# HypnosV3_4.net
KiCad netlist of a schematic drawn in EAGLE
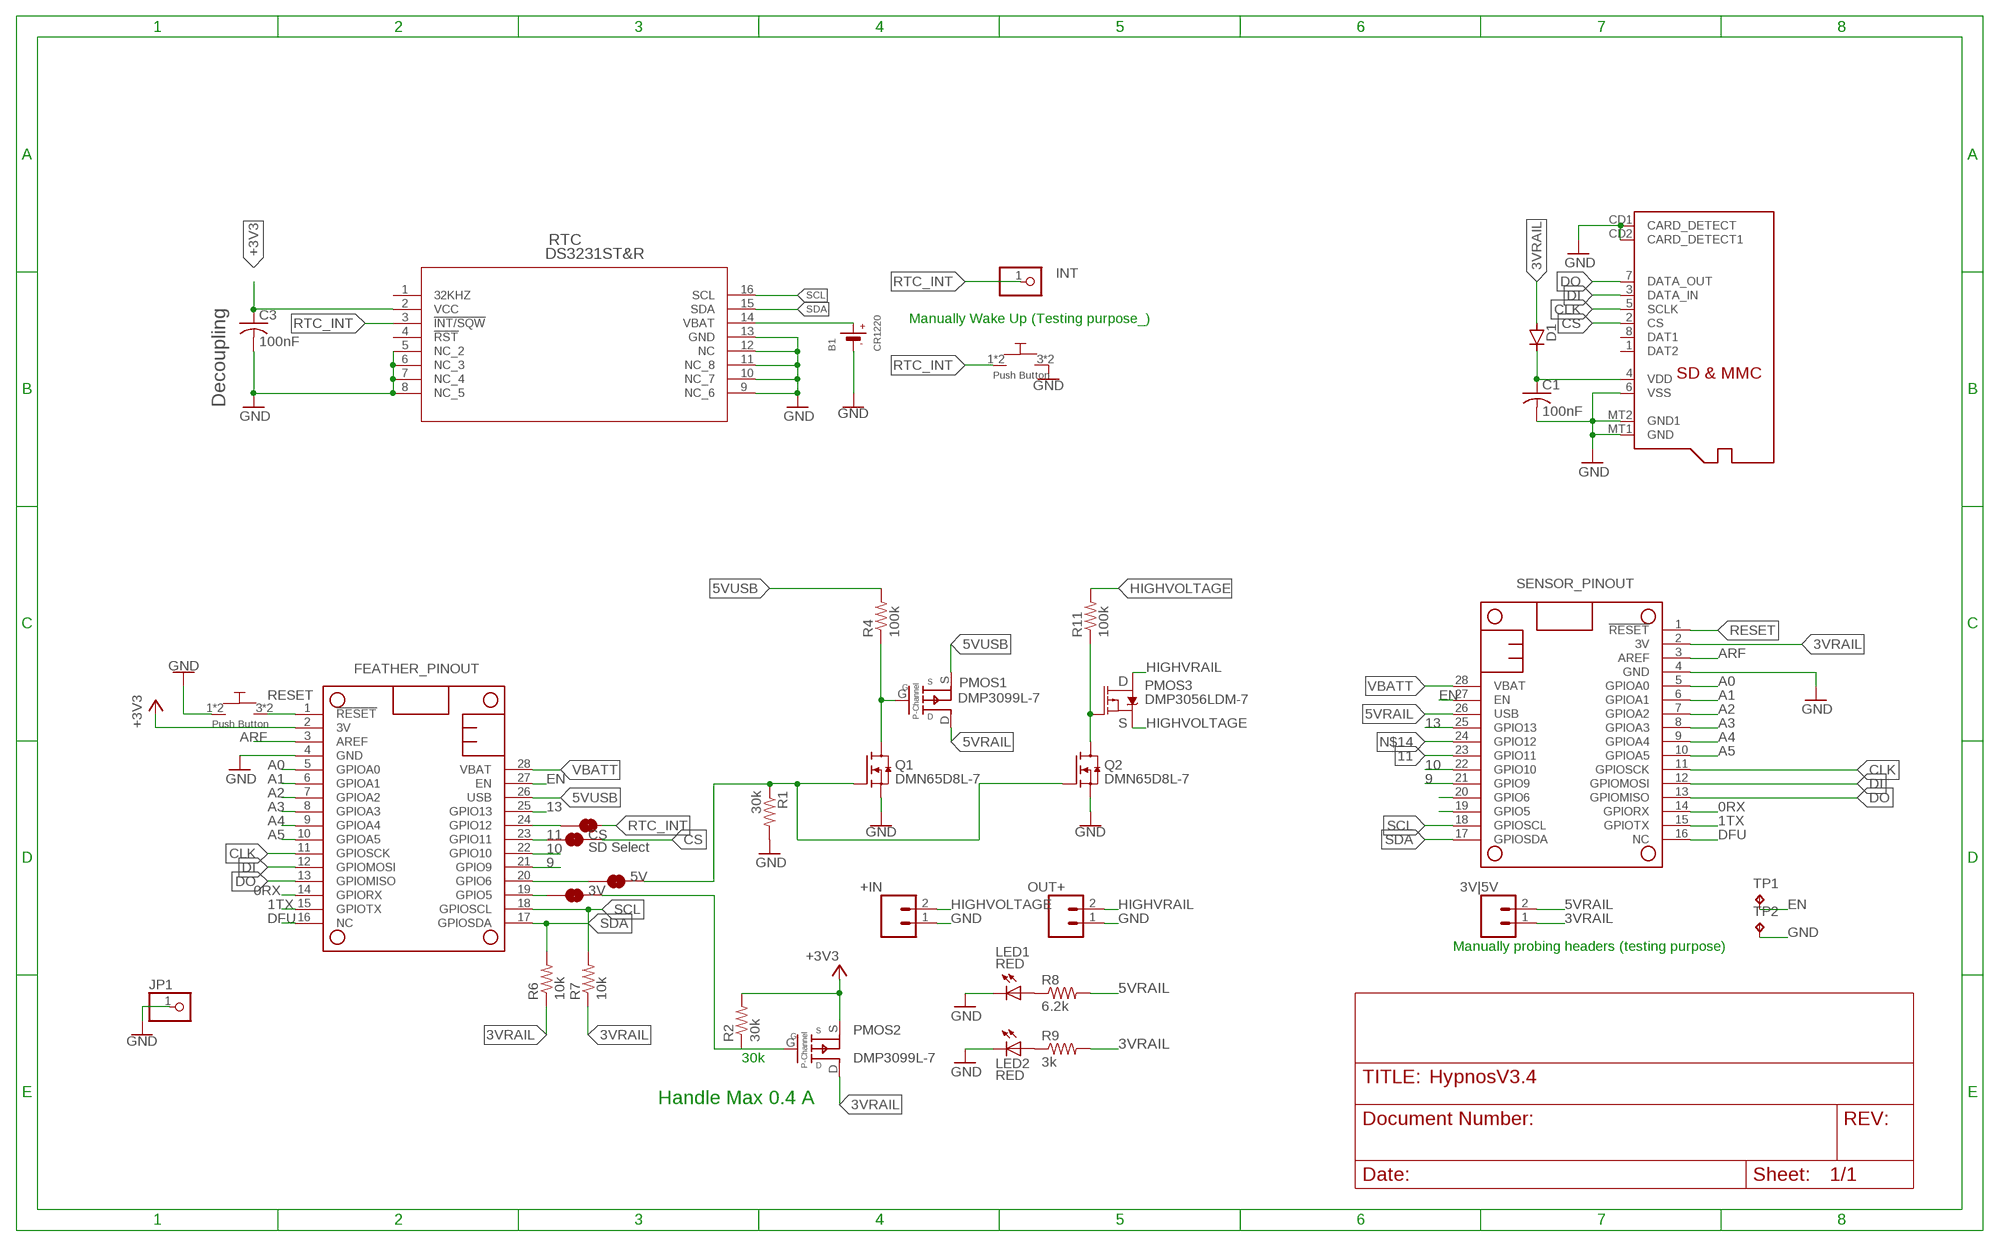
[diagram p0: schematic, sheet 1]

(export (version "E")
  (design (tool "Eeschema 10.0.6"))
  (components
    (comp (ref "+IN")
      (value "HIGHV-IN")
      (footprint "eagle-import:1X02_NO_SILK")
      (libsource (lib "eagle-import") (part "CONN_021X02_NO_SILK"))
    )
    (comp (ref "3V")
      (value "JUMPER-SMT_2_NC_TRACE_SILK")
      (footprint "eagle-import:SMT-JUMPER_2_NC_TRACE_SILK")
      (libsource (lib "eagle-import") (part "JUMPER-SMT_2_NC_TRACE_SILK"))
    )
    (comp (ref "3V|5V")
      (value "CONN_021X02_NO_SILK")
      (footprint "eagle-import:1X02_NO_SILK")
      (libsource (lib "eagle-import") (part "CONN_021X02_NO_SILK"))
    )
    (comp (ref "5V")
      (value "JUMPER-SMT_2_NC_TRACE_SILK")
      (footprint "eagle-import:SMT-JUMPER_2_NC_TRACE_SILK")
      (libsource (lib "eagle-import") (part "JUMPER-SMT_2_NC_TRACE_SILK"))
    )
    (comp (ref "B1")
      (value "CR1220")
      (footprint "eagle-import:CR1220")
      (libsource (lib "eagle-import") (part "BATTERYCR1220_SMT"))
    )
    (comp (ref "C1")
      (value "100nF")
      (footprint "eagle-import:C1206")
      (libsource (lib "eagle-import") (part "C-USC1206"))
    )
    (comp (ref "C3")
      (value "100nF")
      (footprint "eagle-import:C1206")
      (libsource (lib "eagle-import") (part "C-USC1206"))
    )
    (comp (ref "CS")
      (value "SD Select")
      (footprint "eagle-import:SMT-JUMPER_2_NC_TRACE_SILK")
      (libsource (lib "eagle-import") (part "JUMPER-SMT_2_NC_TRACE_SILK"))
    )
    (comp (ref "D1")
      (value "D-SOD123")
      (footprint "eagle-import:SOD123")
      (libsource (lib "eagle-import") (part "D-SOD123"))
    )
    (comp (ref "FEATHERWING")
      (value "SENSOR_PINOUT")
      (footprint "eagle-import:FEATHERWING")
      (libsource (lib "eagle-import") (part "powerboard_FEATHERWING"))
    )
    (comp (ref "INT")
      (value "PINHD-1X1CB")
      (footprint "eagle-import:1X01-CLEANBIG")
      (libsource (lib "eagle-import") (part "PINHD-1X1CB"))
    )
    (comp (ref "JP1")
      (value "PINHD-1X1CB")
      (footprint "eagle-import:1X01-CLEANBIG")
      (libsource (lib "eagle-import") (part "PINHD-1X1CB"))
    )
    (comp (ref "LED1")
      (value "RED")
      (footprint "eagle-import:CHIPLED_0805")
      (libsource (lib "eagle-import") (part "LEDCHIPLED_0805"))
    )
    (comp (ref "LED2")
      (value "RED")
      (footprint "eagle-import:CHIPLED_0805")
      (libsource (lib "eagle-import") (part "LEDCHIPLED_0805"))
    )
    (comp (ref "MICROSD")
      (value "MICROSD")
      (footprint "eagle-import:MICROSD")
      (libsource (lib "eagle-import") (part "MICROSD"))
    )
    (comp (ref "MS2")
      (value "FEATHER_PINOUT")
      (footprint "eagle-import:FEATHERWING")
      (libsource (lib "eagle-import") (part "FEATHERWING"))
    )
    (comp (ref "OUT+")
      (value "HIGHV-OUT")
      (footprint "eagle-import:1X02_NO_SILK")
      (libsource (lib "eagle-import") (part "CONN_021X02_NO_SILK"))
    )
    (comp (ref "PMOS1")
      (value "DMP3099L-7")
      (footprint "eagle-import:SOT-23-3")
      (libsource (lib "eagle-import") (part "SSM3J3228R"))
    )
    (comp (ref "PMOS2")
      (value "DMP3099L-7")
      (footprint "eagle-import:SOT-23-3")
      (libsource (lib "eagle-import") (part "SSM3J3228R"))
    )
    (comp (ref "PMOS3")
      (value "DMP3056LDM-7")
      (footprint "eagle-import:SOT23-6")
      (libsource (lib "eagle-import") (part "P-MOSFET"))
    )
    (comp (ref "Q1")
      (value "DMN65D8L-7")
      (footprint "eagle-import:SOT23-S")
      (libsource (lib "eagle-import") (part "NMOS"))
    )
    (comp (ref "Q2")
      (value "DMN65D8L-7")
      (footprint "eagle-import:SOT23-S")
      (libsource (lib "eagle-import") (part "NMOS"))
    )
    (comp (ref "R1")
      (value "30k")
      (footprint "eagle-import:RES_1206")
      (fields
        (field (name "DIGIKEY_PART_NUMBER") "WSLP-.05TR-ND")
        (field (name "MANUFACTURER") "Vishay Dale")
        (field (name "MPN") "WSLP1206R0500FEA")
        (field (name "CREATED_BY") "PCBLayout.com")
      )
      (libsource (lib "eagle-import") (part "WSLP1206R0500FEA"))
    )
    (comp (ref "R2")
      (value "30k")
      (footprint "eagle-import:RES_1206")
      (fields
        (field (name "DIGIKEY_PART_NUMBER") "WSLP-.05TR-ND")
        (field (name "MANUFACTURER") "Vishay Dale")
        (field (name "MPN") "WSLP1206R0500FEA")
        (field (name "CREATED_BY") "PCBLayout.com")
      )
      (libsource (lib "eagle-import") (part "WSLP1206R0500FEA"))
    )
    (comp (ref "R4")
      (value "100k")
      (footprint "eagle-import:RES_1206")
      (fields
        (field (name "DIGIKEY_PART_NUMBER") "WSLP-.05TR-ND")
        (field (name "MANUFACTURER") "Vishay Dale")
        (field (name "MPN") "WSLP1206R0500FEA")
        (field (name "CREATED_BY") "PCBLayout.com")
      )
      (libsource (lib "eagle-import") (part "WSLP1206R0500FEA"))
    )
    (comp (ref "R6")
      (value "10k")
      (footprint "eagle-import:RES_1206")
      (fields
        (field (name "DIGIKEY_PART_NUMBER") "WSLP-.05TR-ND")
        (field (name "MANUFACTURER") "Vishay Dale")
        (field (name "MPN") "WSLP1206R0500FEA")
        (field (name "CREATED_BY") "PCBLayout.com")
      )
      (libsource (lib "eagle-import") (part "WSLP1206R0500FEA"))
    )
    (comp (ref "R7")
      (value "10k")
      (footprint "eagle-import:RES_1206")
      (fields
        (field (name "DIGIKEY_PART_NUMBER") "WSLP-.05TR-ND")
        (field (name "MANUFACTURER") "Vishay Dale")
        (field (name "MPN") "WSLP1206R0500FEA")
        (field (name "CREATED_BY") "PCBLayout.com")
      )
      (libsource (lib "eagle-import") (part "WSLP1206R0500FEA"))
    )
    (comp (ref "R8")
      (value "6.2k")
      (footprint "eagle-import:RES_1206")
      (fields
        (field (name "DIGIKEY_PART_NUMBER") "WSLP-.05TR-ND")
        (field (name "MANUFACTURER") "Vishay Dale")
        (field (name "MPN") "WSLP1206R0500FEA")
        (field (name "CREATED_BY") "PCBLayout.com")
      )
      (libsource (lib "eagle-import") (part "WSLP1206R0500FEA"))
    )
    (comp (ref "R9")
      (value "3k")
      (footprint "eagle-import:RES_1206")
      (fields
        (field (name "DIGIKEY_PART_NUMBER") "WSLP-.05TR-ND")
        (field (name "MANUFACTURER") "Vishay Dale")
        (field (name "MPN") "WSLP1206R0500FEA")
        (field (name "CREATED_BY") "PCBLayout.com")
      )
      (libsource (lib "eagle-import") (part "WSLP1206R0500FEA"))
    )
    (comp (ref "R11")
      (value "100k")
      (footprint "eagle-import:RES_1206")
      (fields
        (field (name "DIGIKEY_PART_NUMBER") "WSLP-.05TR-ND")
        (field (name "MANUFACTURER") "Vishay Dale")
        (field (name "MPN") "WSLP1206R0500FEA")
        (field (name "CREATED_BY") "PCBLayout.com")
      )
      (libsource (lib "eagle-import") (part "WSLP1206R0500FEA"))
    )
    (comp (ref "RTC")
      (value "DS3231ST&R")
      (footprint "eagle-import:21-0042B_16")
      (fields (field (name "MANUFACTURER_PART_NUMBER") "DS3231S#T&R"))
      (libsource (lib "eagle-import") (part "DS3231ST&R"))
    )
    (comp (ref "RTC_INT")
      (value "JUMPER-SMT_2_NC_TRACE_SILK")
      (footprint "eagle-import:SMT-JUMPER_2_NC_TRACE_SILK")
      (libsource (lib "eagle-import") (part "JUMPER-SMT_2_NC_TRACE_SILK"))
    )
    (comp (ref "TP1")
      (value "TPTP16R")
      (footprint "eagle-import:TP16R")
      (libsource (lib "eagle-import") (part "TPTP16R"))
    )
    (comp (ref "TP2")
      (value "TPTP16R")
      (footprint "eagle-import:TP16R")
      (libsource (lib "eagle-import") (part "TPTP16R"))
    )
    (comp (ref "U$1")
      (value "PUSH_BUTTON")
      (footprint "eagle-import:PUSHBUTTON_SMD")
      (libsource (lib "eagle-import") (part "PUSH_BUTTON"))
    )
    (comp (ref "U$2")
      (value "PUSH_BUTTON")
      (footprint "eagle-import:PUSHBUTTON_SMD")
      (libsource (lib "eagle-import") (part "PUSH_BUTTON"))
    )
  )
  (nets
    (net (code "1") (name "+3V3") (class "Default")
      (node (ref "C3") (pin "1") (pinfunction "1_1") (pintype "passive"))
      (node (ref "MS2") (pin "2") (pinfunction "3V_2") (pintype "power_in"))
      (node (ref "PMOS2") (pin "S") (pinfunction "S_S") (pintype "bidirectional"))
      (node (ref "R2") (pin "2") (pinfunction "2_2") (pintype "passive"))
      (node (ref "RTC") (pin "2") (pinfunction "VCC_2") (pintype "power_in"))
    )
    (net (code "2") (name "/0RX") (class "Default")
      (node (ref "FEATHERWING") (pin "14") (pinfunction "GPIORX_14") (pintype "bidirectional"))
      (node (ref "MS2") (pin "14") (pinfunction "GPIORX_14") (pintype "bidirectional"))
    )
    (net (code "3") (name "/1TX") (class "Default")
      (node (ref "FEATHERWING") (pin "15") (pinfunction "GPIOTX_15") (pintype "bidirectional"))
      (node (ref "MS2") (pin "15") (pinfunction "GPIOTX_15") (pintype "bidirectional"))
    )
    (net (code "4") (name "/9") (class "Default")
      (node (ref "FEATHERWING") (pin "21") (pinfunction "GPIO9_21") (pintype "bidirectional"))
      (node (ref "MS2") (pin "21") (pinfunction "GPIO9_21") (pintype "bidirectional"))
    )
    (net (code "5") (name "/10") (class "Default")
      (node (ref "FEATHERWING") (pin "22") (pinfunction "GPIO10_22") (pintype "bidirectional"))
      (node (ref "MS2") (pin "22") (pinfunction "GPIO10_22") (pintype "bidirectional"))
    )
    (net (code "6") (name "/13") (class "Default")
      (node (ref "FEATHERWING") (pin "25") (pinfunction "GPIO13_25") (pintype "bidirectional"))
      (node (ref "MS2") (pin "25") (pinfunction "GPIO13_25") (pintype "bidirectional"))
    )
    (net (code "7") (name "/A0") (class "Default")
      (node (ref "FEATHERWING") (pin "5") (pinfunction "GPIOA0_5") (pintype "bidirectional"))
      (node (ref "MS2") (pin "5") (pinfunction "GPIOA0_5") (pintype "bidirectional"))
    )
    (net (code "8") (name "/A1") (class "Default")
      (node (ref "FEATHERWING") (pin "6") (pinfunction "GPIOA1_6") (pintype "bidirectional"))
      (node (ref "MS2") (pin "6") (pinfunction "GPIOA1_6") (pintype "bidirectional"))
    )
    (net (code "9") (name "/A2") (class "Default")
      (node (ref "FEATHERWING") (pin "7") (pinfunction "GPIOA2_7") (pintype "bidirectional"))
      (node (ref "MS2") (pin "7") (pinfunction "GPIOA2_7") (pintype "bidirectional"))
    )
    (net (code "10") (name "/A3") (class "Default")
      (node (ref "FEATHERWING") (pin "8") (pinfunction "GPIOA3_8") (pintype "bidirectional"))
      (node (ref "MS2") (pin "8") (pinfunction "GPIOA3_8") (pintype "bidirectional"))
    )
    (net (code "11") (name "/A4") (class "Default")
      (node (ref "FEATHERWING") (pin "9") (pinfunction "GPIOA4_9") (pintype "bidirectional"))
      (node (ref "MS2") (pin "9") (pinfunction "GPIOA4_9") (pintype "bidirectional"))
    )
    (net (code "12") (name "/A5") (class "Default")
      (node (ref "FEATHERWING") (pin "10") (pinfunction "GPIOA5_10") (pintype "bidirectional"))
      (node (ref "MS2") (pin "10") (pinfunction "GPIOA5_10") (pintype "bidirectional"))
    )
    (net (code "13") (name "/ARF") (class "Default")
      (node (ref "FEATHERWING") (pin "3") (pinfunction "AREF_3") (pintype "passive"))
      (node (ref "MS2") (pin "3") (pinfunction "AREF_3") (pintype "passive"))
    )
    (net (code "14") (name "/DFU") (class "Default")
      (node (ref "FEATHERWING") (pin "16") (pinfunction "NC_16") (pintype "passive"))
      (node (ref "MS2") (pin "16") (pinfunction "NC_16") (pintype "passive"))
    )
    (net (code "15") (name "/EN") (class "Default")
      (node (ref "FEATHERWING") (pin "27") (pinfunction "EN_27") (pintype "passive"))
      (node (ref "MS2") (pin "27") (pinfunction "EN_27") (pintype "passive"))
      (node (ref "TP1") (pin "TP") (pinfunction "TP_TP") (pintype "input"))
    )
    (net (code "16") (name "/HIGHVRAIL") (class "Default")
      (node (ref "OUT+") (pin "2") (pinfunction "2_2") (pintype "passive"))
      (node (ref "PMOS3") (pin "1") (pinfunction "D_1") (pintype "bidirectional"))
      (node (ref "PMOS3") (pin "2") (pinfunction "D_2") (pintype "bidirectional"))
      (node (ref "PMOS3") (pin "5") (pinfunction "D_5") (pintype "bidirectional"))
      (node (ref "PMOS3") (pin "6") (pinfunction "D_6") (pintype "bidirectional"))
    )
    (net (code "17") (name "3VRAIL") (class "Default")
      (node (ref "3V|5V") (pin "1") (pinfunction "1_1") (pintype "passive"))
      (node (ref "D1") (pin "2") (pinfunction "A_2") (pintype "passive"))
      (node (ref "FEATHERWING") (pin "2") (pinfunction "3V_2") (pintype "power_in"))
      (node (ref "PMOS2") (pin "D") (pinfunction "D_D") (pintype "bidirectional"))
      (node (ref "R6") (pin "1") (pinfunction "1_1") (pintype "passive"))
      (node (ref "R7") (pin "1") (pinfunction "1_1") (pintype "passive"))
      (node (ref "R9") (pin "2") (pinfunction "2_2") (pintype "passive"))
    )
    (net (code "18") (name "5VRAIL") (class "Default")
      (node (ref "3V|5V") (pin "2") (pinfunction "2_2") (pintype "passive"))
      (node (ref "FEATHERWING") (pin "26") (pinfunction "USB_26") (pintype "power_in"))
      (node (ref "PMOS1") (pin "D") (pinfunction "D_D") (pintype "bidirectional"))
      (node (ref "R8") (pin "2") (pinfunction "2_2") (pintype "passive"))
    )
    (net (code "19") (name "5VUSB") (class "Default")
      (node (ref "MS2") (pin "26") (pinfunction "USB_26") (pintype "power_in"))
      (node (ref "PMOS1") (pin "S") (pinfunction "S_S") (pintype "bidirectional"))
      (node (ref "R4") (pin "2") (pinfunction "2_2") (pintype "passive"))
    )
    (net (code "20") (name "11") (class "Default")
      (node (ref "CS") (pin "1") (pinfunction "1_1") (pintype "passive"))
      (node (ref "FEATHERWING") (pin "23") (pinfunction "GPIO11_23") (pintype "bidirectional"))
      (node (ref "MS2") (pin "23") (pinfunction "GPIO11_23") (pintype "bidirectional"))
    )
    (net (code "21") (name "CLK") (class "Default")
      (node (ref "FEATHERWING") (pin "11") (pinfunction "GPIOSCK_11") (pintype "bidirectional"))
      (node (ref "MICROSD") (pin "5") (pinfunction "SCLK_5") (pintype "input"))
      (node (ref "MS2") (pin "11") (pinfunction "GPIOSCK_11") (pintype "bidirectional"))
    )
    (net (code "22") (name "CS") (class "Default")
      (node (ref "CS") (pin "2") (pinfunction "2_2") (pintype "passive"))
      (node (ref "MICROSD") (pin "2") (pinfunction "CS_2") (pintype "input"))
    )
    (net (code "23") (name "DI") (class "Default")
      (node (ref "FEATHERWING") (pin "12") (pinfunction "GPIOMOSI_12") (pintype "bidirectional"))
      (node (ref "MICROSD") (pin "3") (pinfunction "DATA_IN_3") (pintype "input"))
      (node (ref "MS2") (pin "12") (pinfunction "GPIOMOSI_12") (pintype "bidirectional"))
    )
    (net (code "24") (name "DO") (class "Default")
      (node (ref "FEATHERWING") (pin "13") (pinfunction "GPIOMISO_13") (pintype "bidirectional"))
      (node (ref "MICROSD") (pin "7") (pinfunction "DATA_OUT_7") (pintype "output"))
      (node (ref "MS2") (pin "13") (pinfunction "GPIOMISO_13") (pintype "bidirectional"))
    )
    (net (code "25") (name "GND") (class "Default")
      (node (ref "+IN") (pin "1") (pinfunction "1_1") (pintype "passive"))
      (node (ref "B1") (pin "-") (pinfunction "-_-") (pintype "passive"))
      (node (ref "C1") (pin "2") (pinfunction "2_2") (pintype "passive"))
      (node (ref "C3") (pin "2") (pinfunction "2_2") (pintype "passive"))
      (node (ref "FEATHERWING") (pin "4") (pinfunction "GND_4") (pintype "power_in"))
      (node (ref "JP1") (pin "1") (pinfunction "1_1") (pintype "passive"))
      (node (ref "LED1") (pin "C") (pinfunction "C_C") (pintype "passive"))
      (node (ref "LED2") (pin "C") (pinfunction "C_C") (pintype "passive"))
      (node (ref "MICROSD") (pin "6") (pinfunction "VSS_6") (pintype "power_in"))
      (node (ref "MICROSD") (pin "CD1") (pinfunction "CARD_DETECT_CD1") (pintype "passive"))
      (node (ref "MICROSD") (pin "CD2") (pinfunction "CARD_DETECT1_CD2") (pintype "passive"))
      (node (ref "MICROSD") (pin "MT1") (pinfunction "GND_MT1") (pintype "power_in"))
      (node (ref "MICROSD") (pin "MT2") (pinfunction "GND1_MT2") (pintype "power_in"))
      (node (ref "MS2") (pin "4") (pinfunction "GND_4") (pintype "power_in"))
      (node (ref "OUT+") (pin "1") (pinfunction "1_1") (pintype "passive"))
      (node (ref "Q1") (pin "2") (pinfunction "S_2") (pintype "passive"))
      (node (ref "Q2") (pin "2") (pinfunction "S_2") (pintype "passive"))
      (node (ref "R1") (pin "2") (pinfunction "2_2") (pintype "passive"))
      (node (ref "RTC") (pin "10") (pinfunction "NC_7_10") (pintype "passive"))
      (node (ref "RTC") (pin "11") (pinfunction "NC_8_11") (pintype "passive"))
      (node (ref "RTC") (pin "12") (pinfunction "NC_12") (pintype "passive"))
      (node (ref "RTC") (pin "13") (pinfunction "GND_13") (pintype "power_in"))
      (node (ref "RTC") (pin "5") (pinfunction "NC_2_5") (pintype "passive"))
      (node (ref "RTC") (pin "6") (pinfunction "NC_3_6") (pintype "passive"))
      (node (ref "RTC") (pin "7") (pinfunction "NC_4_7") (pintype "passive"))
      (node (ref "RTC") (pin "8") (pinfunction "NC_5_8") (pintype "passive"))
      (node (ref "RTC") (pin "9") (pinfunction "NC_6_9") (pintype "passive"))
      (node (ref "TP2") (pin "TP") (pinfunction "TP_TP") (pintype "input"))
      (node (ref "U$1") (pin "1") (pinfunction "P$1_1") (pintype "bidirectional"))
      (node (ref "U$1") (pin "2") (pinfunction "P$1_2") (pintype "bidirectional"))
      (node (ref "U$2") (pin "3") (pinfunction "P$2_3") (pintype "bidirectional"))
      (node (ref "U$2") (pin "4") (pinfunction "P$2_4") (pintype "bidirectional"))
    )
    (net (code "26") (name "HIGHVOLTAGE") (class "Default")
      (node (ref "+IN") (pin "2") (pinfunction "2_2") (pintype "passive"))
      (node (ref "PMOS3") (pin "4") (pinfunction "S_4") (pintype "bidirectional"))
      (node (ref "R11") (pin "2") (pinfunction "2_2") (pintype "passive"))
    )
    (net (code "27") (name "N$14") (class "Default")
      (node (ref "FEATHERWING") (pin "24") (pinfunction "GPIO12_24") (pintype "bidirectional"))
      (node (ref "MS2") (pin "24") (pinfunction "GPIO12_24") (pintype "bidirectional"))
      (node (ref "RTC_INT") (pin "1") (pinfunction "1_1") (pintype "passive"))
    )
    (net (code "28") (name "Net-(3V-Pad2)") (class "Default")
      (node (ref "3V") (pin "2") (pinfunction "2_2") (pintype "passive"))
      (node (ref "PMOS2") (pin "G") (pinfunction "G_G") (pintype "bidirectional"))
      (node (ref "R2") (pin "1") (pinfunction "1_1") (pintype "passive"))
    )
    (net (code "29") (name "Net-(B1-+)") (class "Default")
      (node (ref "B1") (pin "+$1") (pinfunction "+_+$1") (pintype "passive"))
      (node (ref "RTC") (pin "14") (pinfunction "VBAT_14") (pintype "power_in"))
    )
    (net (code "30") (name "Net-(D1-C)") (class "Default")
      (node (ref "C1") (pin "1") (pinfunction "1_1") (pintype "passive"))
      (node (ref "D1") (pin "1") (pinfunction "C_1") (pintype "passive"))
      (node (ref "MICROSD") (pin "4") (pinfunction "VDD_4") (pintype "power_in"))
    )
    (net (code "31") (name "Net-(LED1-PadA)") (class "Default")
      (node (ref "LED1") (pin "A") (pinfunction "A_A") (pintype "passive"))
      (node (ref "R8") (pin "1") (pinfunction "1_1") (pintype "passive"))
    )
    (net (code "32") (name "Net-(LED2-PadA)") (class "Default")
      (node (ref "LED2") (pin "A") (pinfunction "A_A") (pintype "passive"))
      (node (ref "R9") (pin "1") (pinfunction "1_1") (pintype "passive"))
    )
    (net (code "33") (name "Net-(MS2-GPIO5)") (class "Default")
      (node (ref "3V") (pin "1") (pinfunction "1_1") (pintype "passive"))
      (node (ref "MS2") (pin "19") (pinfunction "GPIO5_19") (pintype "bidirectional"))
    )
    (net (code "34") (name "Net-(MS2-GPIO6)") (class "Default")
      (node (ref "5V") (pin "1") (pinfunction "1_1") (pintype "passive"))
      (node (ref "MS2") (pin "20") (pinfunction "GPIO6_20") (pintype "bidirectional"))
    )
    (net (code "35") (name "Net-(PMOS3-G)") (class "Default")
      (node (ref "PMOS3") (pin "3") (pinfunction "G_3") (pintype "bidirectional"))
      (node (ref "Q2") (pin "3") (pinfunction "D_3") (pintype "passive"))
      (node (ref "R11") (pin "1") (pinfunction "1_1") (pintype "passive"))
    )
    (net (code "36") (name "Net-(Q1-D)") (class "Default")
      (node (ref "PMOS1") (pin "G") (pinfunction "G_G") (pintype "bidirectional"))
      (node (ref "Q1") (pin "3") (pinfunction "D_3") (pintype "passive"))
      (node (ref "R4") (pin "1") (pinfunction "1_1") (pintype "passive"))
    )
    (net (code "37") (name "Net-(Q1-G)") (class "Default")
      (node (ref "5V") (pin "2") (pinfunction "2_2") (pintype "passive"))
      (node (ref "Q1") (pin "1") (pinfunction "G_1") (pintype "passive"))
      (node (ref "Q2") (pin "1") (pinfunction "G_1") (pintype "passive"))
      (node (ref "R1") (pin "1") (pinfunction "1_1") (pintype "passive"))
    )
    (net (code "38") (name "RESET") (class "Default")
      (node (ref "FEATHERWING") (pin "1") (pinfunction "~{RESET}_1") (pintype "input"))
      (node (ref "MS2") (pin "1") (pinfunction "~{RESET}_1") (pintype "input"))
      (node (ref "U$1") (pin "3") (pinfunction "P$2_3") (pintype "bidirectional"))
      (node (ref "U$1") (pin "4") (pinfunction "P$2_4") (pintype "bidirectional"))
    )
    (net (code "39") (name "RTC_INT") (class "Default")
      (node (ref "INT") (pin "1") (pinfunction "1_1") (pintype "passive"))
      (node (ref "RTC") (pin "3") (pinfunction "~{INT/SQW}_3") (pintype "passive"))
      (node (ref "RTC_INT") (pin "2") (pinfunction "2_2") (pintype "passive"))
      (node (ref "U$2") (pin "1") (pinfunction "P$1_1") (pintype "bidirectional"))
      (node (ref "U$2") (pin "2") (pinfunction "P$1_2") (pintype "bidirectional"))
    )
    (net (code "40") (name "SCL") (class "Default")
      (node (ref "FEATHERWING") (pin "18") (pinfunction "GPIOSCL_18") (pintype "bidirectional"))
      (node (ref "MS2") (pin "18") (pinfunction "GPIOSCL_18") (pintype "bidirectional"))
      (node (ref "R7") (pin "2") (pinfunction "2_2") (pintype "passive"))
      (node (ref "RTC") (pin "16") (pinfunction "SCL_16") (pintype "passive"))
    )
    (net (code "41") (name "SDA") (class "Default")
      (node (ref "FEATHERWING") (pin "17") (pinfunction "GPIOSDA_17") (pintype "bidirectional"))
      (node (ref "MS2") (pin "17") (pinfunction "GPIOSDA_17") (pintype "bidirectional"))
      (node (ref "R6") (pin "2") (pinfunction "2_2") (pintype "passive"))
      (node (ref "RTC") (pin "15") (pinfunction "SDA_15") (pintype "passive"))
    )
    (net (code "42") (name "VBATT") (class "Default")
      (node (ref "FEATHERWING") (pin "28") (pinfunction "VBAT_28") (pintype "power_in"))
      (node (ref "MS2") (pin "28") (pinfunction "VBAT_28") (pintype "power_in"))
    )
    (net (code "43") (name "unconnected-(FEATHERWING-GPIO5-Pad19)") (class "Default")
      (node (ref "FEATHERWING") (pin "19") (pinfunction "GPIO5_19") (pintype "bidirectional"))
    )
    (net (code "44") (name "unconnected-(FEATHERWING-GPIO6-Pad20)") (class "Default")
      (node (ref "FEATHERWING") (pin "20") (pinfunction "GPIO6_20") (pintype "bidirectional"))
    )
    (net (code "45") (name "unconnected-(MICROSD-DAT1-Pad8)") (class "Default")
      (node (ref "MICROSD") (pin "8") (pinfunction "DAT1_8") (pintype "bidirectional"))
    )
    (net (code "46") (name "unconnected-(MICROSD-DAT2-Pad1)") (class "Default")
      (node (ref "MICROSD") (pin "1") (pinfunction "DAT2_1") (pintype "bidirectional"))
    )
    (net (code "47") (name "unconnected-(RTC-32KHZ-Pad1)") (class "Default")
      (node (ref "RTC") (pin "1") (pinfunction "32KHZ_1") (pintype "passive"))
    )
    (net (code "48") (name "unconnected-(RTC-~{RST}-Pad4)") (class "Default")
      (node (ref "RTC") (pin "4") (pinfunction "~{RST}_4") (pintype "passive"))
    )
  )
)
